# 2.net
KiCad netlist of a schematic drawn in EAGLE
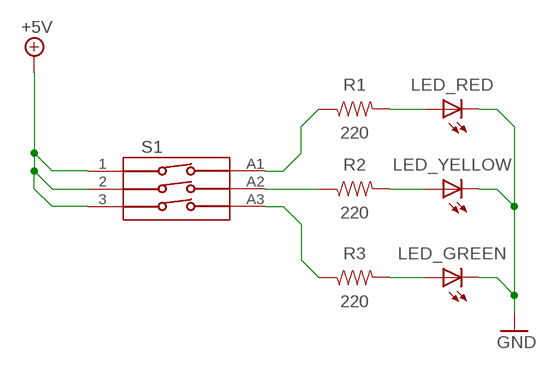
[diagram p0: schematic, sheet 1]

(export (version "E")
  (design (tool "Eeschema 10.0.6"))
  (components
    (comp (ref "LED_GREEN")
      (value "LED5MM")
      (footprint "eagle-import:LED5MM")
      (libsource (lib "eagle-import") (part "LED5MM"))
    )
    (comp (ref "LED_RED")
      (value "LED5MM")
      (footprint "eagle-import:LED5MM")
      (libsource (lib "eagle-import") (part "LED5MM"))
    )
    (comp (ref "LED_YELLOW")
      (value "LED5MM")
      (footprint "eagle-import:LED5MM")
      (libsource (lib "eagle-import") (part "LED5MM"))
    )
    (comp (ref "R1")
      (value "220")
      (footprint "eagle-import:AXIAL-0.3")
      (libsource (lib "eagle-import") (part "100OHM-HORIZ-1/4W-1%"))
    )
    (comp (ref "R2")
      (value "220")
      (footprint "eagle-import:AXIAL-0.3")
      (libsource (lib "eagle-import") (part "100OHM-HORIZ-1/4W-1%"))
    )
    (comp (ref "R3")
      (value "220")
      (footprint "eagle-import:AXIAL-0.3")
      (libsource (lib "eagle-import") (part "100OHM-HORIZ-1/4W-1%"))
    )
    (comp (ref "S1")
      (value "418117170903")
      (footprint "eagle-import:418117170903")
      (libsource (lib "eagle-import") (part "418117170903"))
    )
  )
  (nets
    (net (code "1") (name "+5V") (class "Default")
      (node (ref "S1") (pin "1") (pinfunction "1_1") (pintype "passive"))
      (node (ref "S1") (pin "2") (pinfunction "2_2") (pintype "passive"))
      (node (ref "S1") (pin "3") (pinfunction "3_3") (pintype "passive"))
    )
    (net (code "2") (name "GND") (class "Default")
      (node (ref "LED_GREEN") (pin "K") (pinfunction "C_K") (pintype "passive"))
      (node (ref "LED_RED") (pin "K") (pinfunction "C_K") (pintype "passive"))
      (node (ref "LED_YELLOW") (pin "K") (pinfunction "C_K") (pintype "passive"))
    )
    (net (code "3") (name "Net-(R1-1)") (class "Default")
      (node (ref "R1") (pin "P$1") (pinfunction "1_P$1") (pintype "passive"))
      (node (ref "S1") (pin "A1") (pinfunction "6_A1") (pintype "passive"))
    )
    (net (code "4") (name "Net-(R1-2)") (class "Default")
      (node (ref "LED_RED") (pin "A") (pinfunction "A_A") (pintype "passive"))
      (node (ref "R1") (pin "P$2") (pinfunction "2_P$2") (pintype "passive"))
    )
    (net (code "5") (name "Net-(R2-1)") (class "Default")
      (node (ref "R2") (pin "P$1") (pinfunction "1_P$1") (pintype "passive"))
      (node (ref "S1") (pin "A2") (pinfunction "5_A2") (pintype "passive"))
    )
    (net (code "6") (name "Net-(R2-2)") (class "Default")
      (node (ref "LED_YELLOW") (pin "A") (pinfunction "A_A") (pintype "passive"))
      (node (ref "R2") (pin "P$2") (pinfunction "2_P$2") (pintype "passive"))
    )
    (net (code "7") (name "Net-(R3-1)") (class "Default")
      (node (ref "R3") (pin "P$1") (pinfunction "1_P$1") (pintype "passive"))
      (node (ref "S1") (pin "A3") (pinfunction "4_A3") (pintype "passive"))
    )
    (net (code "8") (name "Net-(R3-2)") (class "Default")
      (node (ref "LED_GREEN") (pin "A") (pinfunction "A_A") (pintype "passive"))
      (node (ref "R3") (pin "P$2") (pinfunction "2_P$2") (pintype "passive"))
    )
  )
)
